# 14_JTAG_DBG.net
KiCad netlist of a schematic drawn in Altium Designer
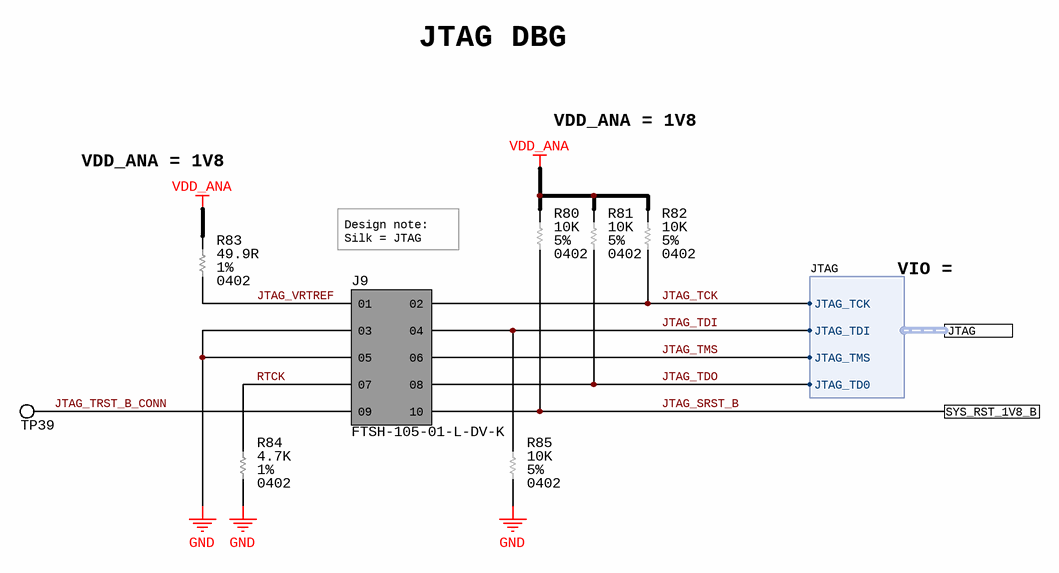
[diagram p0: 14_JTAG_DBG.SchDoc]

(export (version "E")
  (design (tool "Eeschema 10.0.6"))
  (components
    (comp (ref "J9")
      (value "FTSH-105-01-L-DV-K")
      (footprint "SAMTEC_FTSH-105-XX-X-DV")
      (description "Pin Header, Board-to-Board, Wire-to-Board, 1.27 mm, 2 Rows, 10 Contacts, Surface Mount")
      (fields (field (name "MANUFACTURER") "Samtec"))
      (libsource (lib "Electronic Devices_LIB") (part "CONN_HEADER_JTAG_10P_2R_FTSH-105-01-L-DV-K"))
    )
    (comp (ref "R80")
      (value "ERJ-2GEJ103X")
      (footprint "RES_0402_RESC1005X04N")
      (description "Res Thick Film 0402 10K Ohm 5% 1/10W ±200ppm/°C Molded SMD Punched Carrier T/R")
      (fields
        (field (name "MANUFACTURER") "Panasonic")
        (field (name "TOLERANCE") "5%")
        (field (name "RESISTANCE") "10K")
        (field (name "CASE/PACKAGE") "0402")
      )
      (libsource (lib "Electronic Devices_LIB") (part "RES_10K_5%_100mW_0402"))
    )
    (comp (ref "R81")
      (value "ERJ-2GEJ103X")
      (footprint "RES_0402_RESC1005X04N")
      (description "Res Thick Film 0402 10K Ohm 5% 1/10W ±200ppm/°C Molded SMD Punched Carrier T/R")
      (fields
        (field (name "MANUFACTURER") "Panasonic")
        (field (name "TOLERANCE") "5%")
        (field (name "RESISTANCE") "10K")
        (field (name "CASE/PACKAGE") "0402")
      )
      (libsource (lib "Electronic Devices_LIB") (part "RES_10K_5%_100mW_0402"))
    )
    (comp (ref "R82")
      (value "ERJ-2GEJ103X")
      (footprint "RES_0402_RESC1005X04N")
      (description "Res Thick Film 0402 10K Ohm 5% 1/10W ±200ppm/°C Molded SMD Punched Carrier T/R")
      (fields
        (field (name "MANUFACTURER") "Panasonic")
        (field (name "TOLERANCE") "5%")
        (field (name "RESISTANCE") "10K")
        (field (name "CASE/PACKAGE") "0402")
      )
      (libsource (lib "Electronic Devices_LIB") (part "RES_10K_5%_100mW_0402"))
    )
    (comp (ref "R83")
      (value "CR0402-FX-49R9GLF")
      (footprint "RES_0402_RESC1005X04N")
      (description "SMD Chip Resistor, 49.9 Ohm, ± 1%, 63 mW, 0402 [1005 Metric], Thick Film, General Purpose")
      (fields
        (field (name "MANUFACTURER") "Bourns")
        (field (name "RESISTANCE") "49.9R")
        (field (name "TOLERANCE") "1%")
        (field (name "CASE/PACKAGE") "0402")
      )
      (libsource (lib "Electronic Devices_LIB") (part "RES_49.9R_1%_63mW_0402"))
    )
    (comp (ref "R84")
      (value "ERJ-2RKF4701X")
      (footprint "RES_0402_RESC1005X04N")
      (description "Res Thick Film 0402 4.7K Ohm 1% 0.1W ±100ppm/°C Molded SMD Punched Carrier T/R")
      (fields
        (field (name "MANUFACTURER") "Panasonic")
        (field (name "TOLERANCE") "1%")
        (field (name "CASE CODE (IMPERIAL)") "0402")
        (field (name "RESISTANCE") "4.7K")
      )
      (libsource (lib "Electronic Devices_LIB") (part "RES_4.7K_1%_100mW_0402"))
    )
    (comp (ref "R85")
      (value "ERJ-2GEJ103X")
      (footprint "RES_0402_RESC1005X04N")
      (description "Res Thick Film 0402 10K Ohm 5% 1/10W ±200ppm/°C Molded SMD Punched Carrier T/R")
      (fields
        (field (name "MANUFACTURER") "Panasonic")
        (field (name "TOLERANCE") "5%")
        (field (name "RESISTANCE") "10K")
        (field (name "CASE/PACKAGE") "0402")
      )
      (libsource (lib "Electronic Devices_LIB") (part "RES_10K_5%_100mW_0402"))
    )
    (comp (ref "TP39")
      (value "NO COMPONENT")
      (footprint "TP_PAD_0.5MM_SMD_ROUND")
      (description "Test Point, SMD pad, round, 1.5mm, 1.6mm, 3mm diameter")
      (libsource (lib "Electronic Devices_LIB") (part "TP_PAD_SMD_SMALL"))
    )
  )
  (nets
    (net (code "2") (name "/JTAG_SRST_B") (class "Default")
      (node (ref "J9") (pin "10") (pinfunction "10_10") (pintype "passive"))
      (node (ref "R80") (pin "1") (pinfunction "1_1") (pintype "passive"))
    )
    (net (code "3") (name "/JTAG_TCK") (class "Default")
      (node (ref "J9") (pin "02") (pinfunction "02_02") (pintype "passive"))
      (node (ref "R82") (pin "1") (pinfunction "1_1") (pintype "passive"))
    )
    (net (code "4") (name "/JTAG_TDI") (class "Default")
      (node (ref "J9") (pin "04") (pinfunction "04_04") (pintype "passive"))
      (node (ref "R85") (pin "2") (pinfunction "2_2") (pintype "passive"))
    )
    (net (code "5") (name "/JTAG_TDO") (class "Default")
      (node (ref "J9") (pin "08") (pinfunction "08_08") (pintype "passive"))
      (node (ref "R81") (pin "1") (pinfunction "1_1") (pintype "passive"))
    )
    (net (code "6") (name "/JTAG_TMS") (class "Default")
      (node (ref "J9") (pin "06") (pinfunction "06_06") (pintype "passive"))
    )
    (net (code "7") (name "/JTAG_TRST_B_CONN") (class "Default")
      (node (ref "J9") (pin "09") (pinfunction "09_09") (pintype "passive"))
      (node (ref "TP39") (pin "1") (pinfunction "1_1") (pintype "passive"))
    )
    (net (code "8") (name "/JTAG_VRTREF") (class "Default")
      (node (ref "J9") (pin "01") (pinfunction "01_01") (pintype "passive"))
      (node (ref "R83") (pin "1") (pinfunction "1_1") (pintype "passive"))
    )
    (net (code "9") (name "/RTCK") (class "Default")
      (node (ref "J9") (pin "07") (pinfunction "07_07") (pintype "passive"))
      (node (ref "R84") (pin "2") (pinfunction "2_2") (pintype "passive"))
    )
    (net (code "11") (name "GND") (class "Default")
      (node (ref "J9") (pin "03") (pinfunction "03_03") (pintype "passive"))
      (node (ref "J9") (pin "05") (pinfunction "05_05") (pintype "passive"))
      (node (ref "R84") (pin "1") (pinfunction "1_1") (pintype "passive"))
      (node (ref "R85") (pin "1") (pinfunction "1_1") (pintype "passive"))
    )
    (net (code "12") (name "VDD_ANA") (class "Default")
      (node (ref "R80") (pin "2") (pinfunction "2_2") (pintype "passive"))
      (node (ref "R81") (pin "2") (pinfunction "2_2") (pintype "passive"))
      (node (ref "R82") (pin "2") (pinfunction "2_2") (pintype "passive"))
      (node (ref "R83") (pin "2") (pinfunction "2_2") (pintype "passive"))
    )
  )
)
